# SCH_Aether_Zero_R0_5.net
KiCad netlist of a schematic drawn in EasyEDA
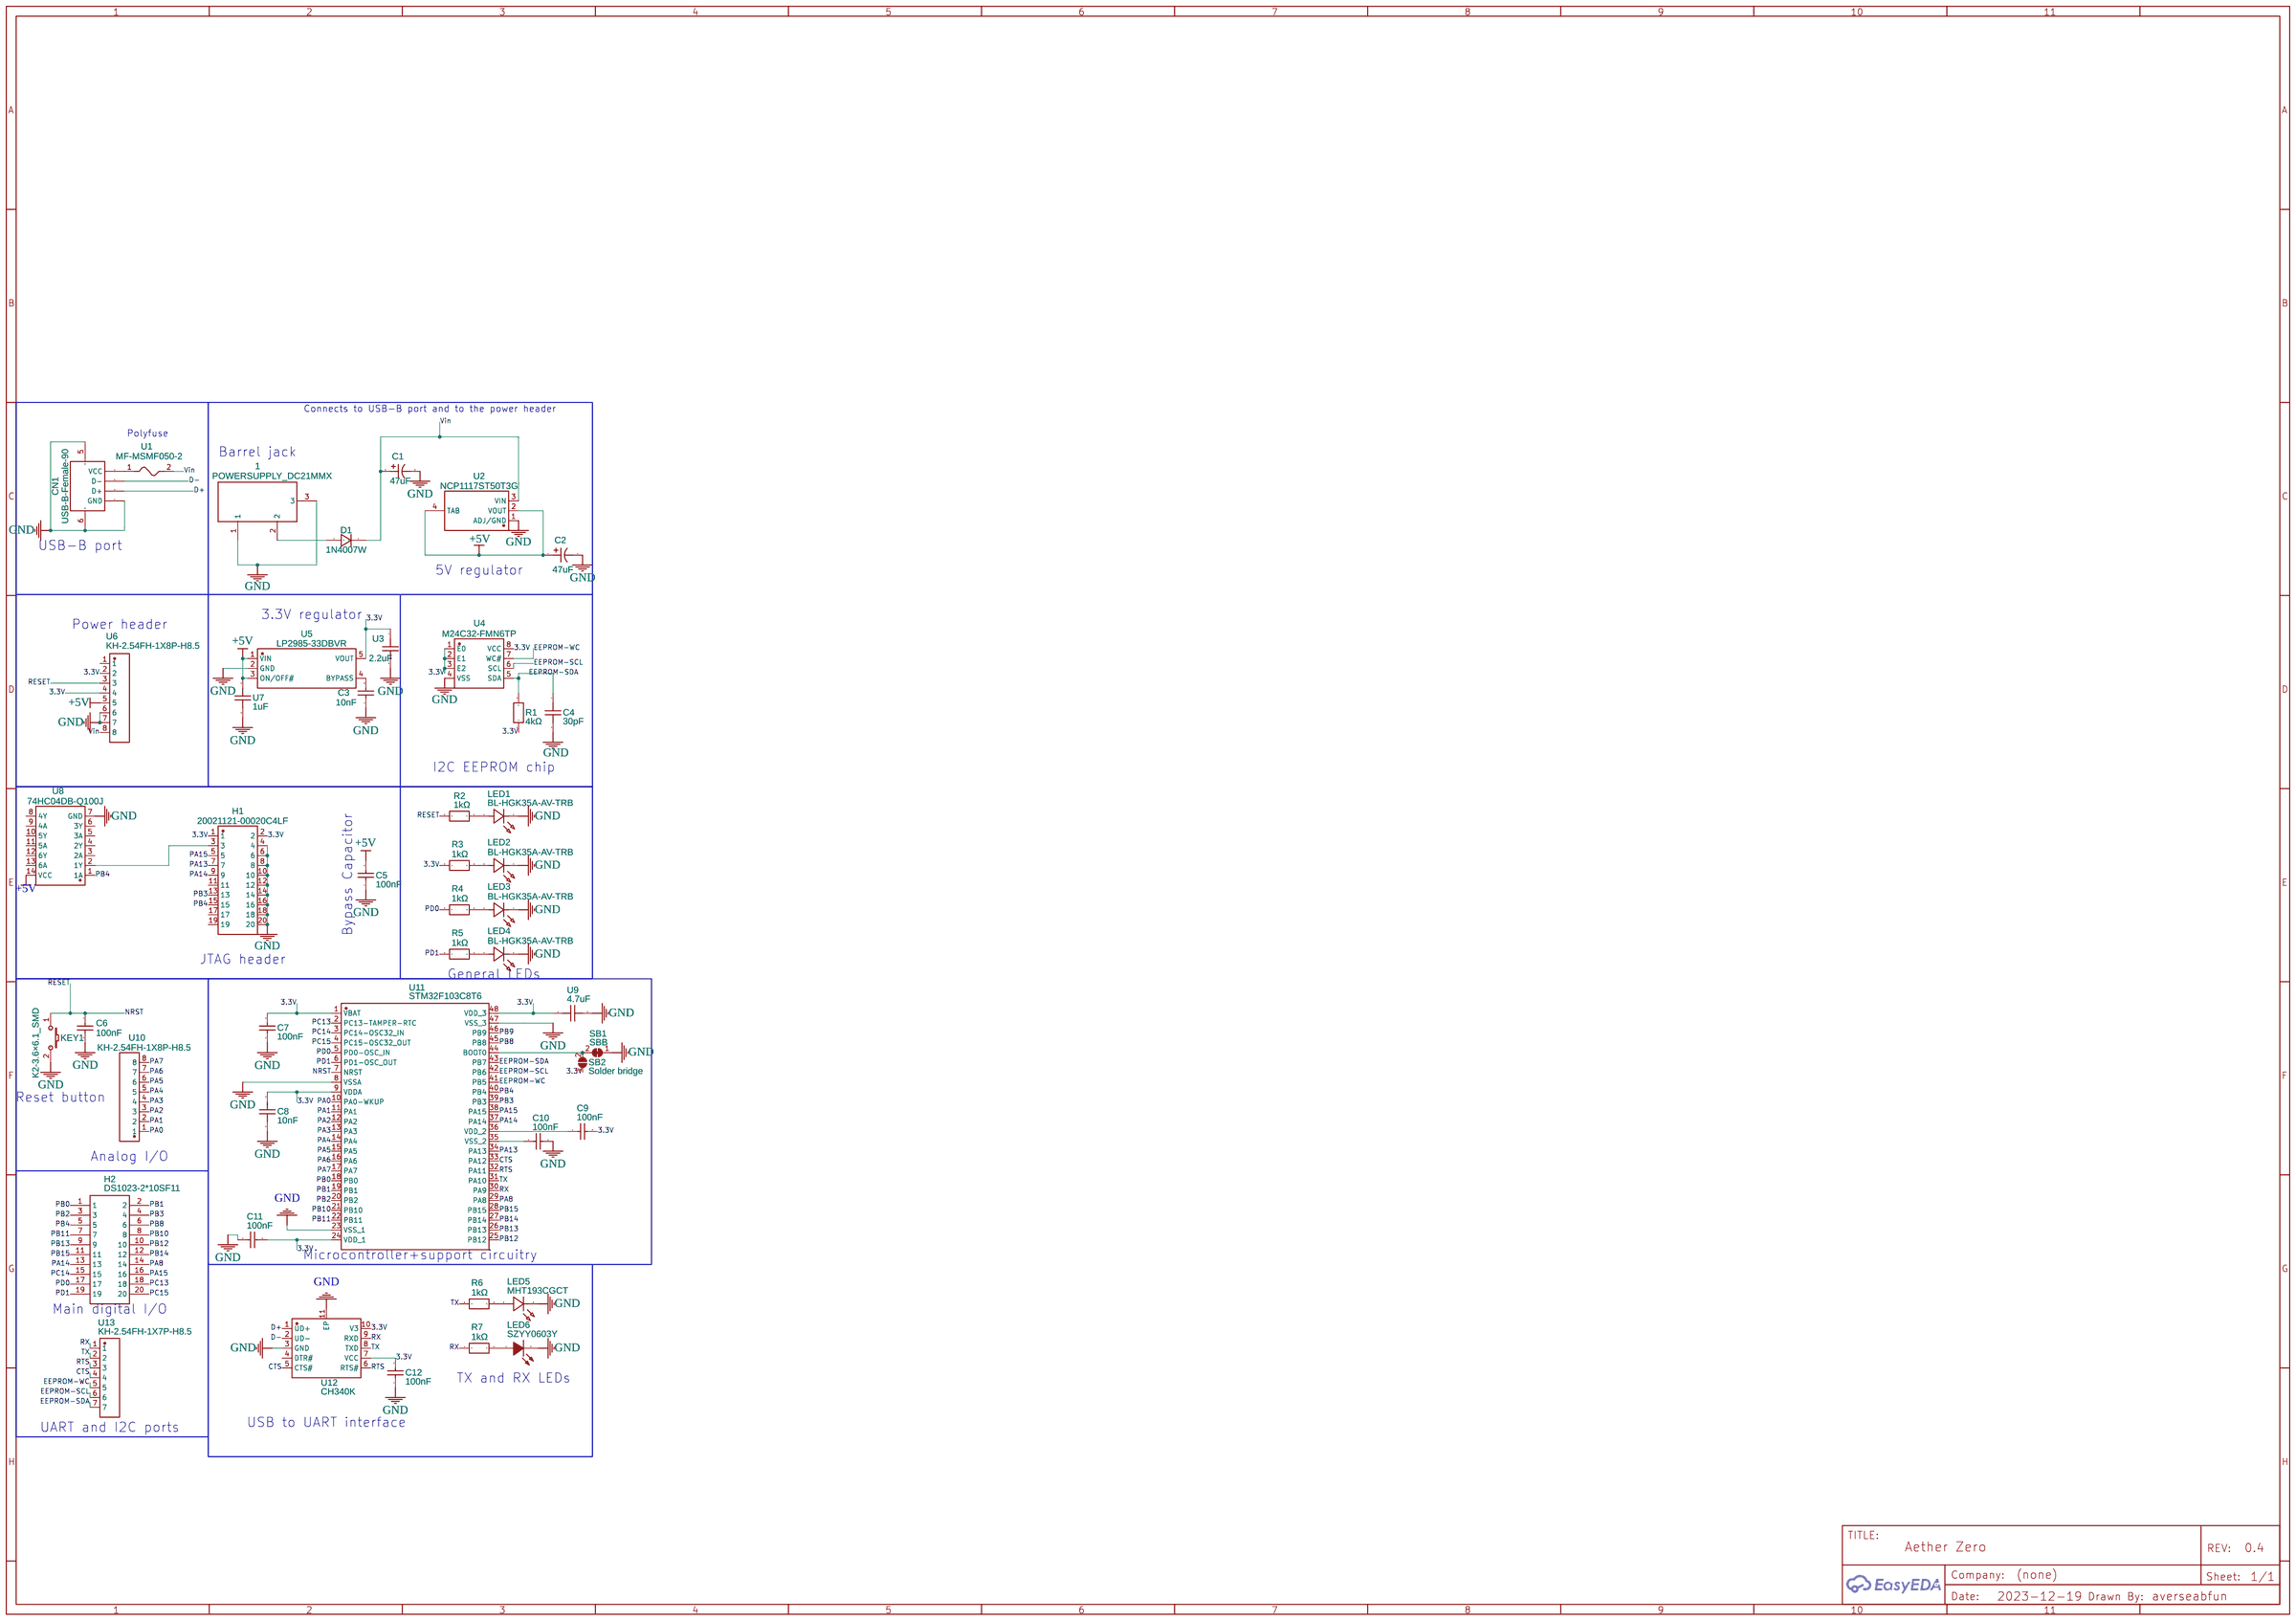
[diagram p0: schematic sheet]

(export (version "E")
  (design (tool "Eeschema 10.0.6"))
  (components
    (comp (ref "1") (value "POWERSUPPLY_DC21MMX") (libsource (lib "") (part "POWERSUPPLY_DC21MMX")))
    (comp (ref "C1")
      (value "47uF")
      (fields
        (field (name "Manufacturer Part") "RVT47UF35V67RV0039")
        (field (name "Manufacturer") "KNSCHA(科尼盛)")
      )
      (libsource (lib "") (part "RVT47UF35V67RV0039"))
    )
    (comp (ref "C2")
      (value "47uF")
      (fields
        (field (name "Manufacturer Part") "RVT47UF35V67RV0039")
        (field (name "Manufacturer") "KNSCHA(科尼盛)")
      )
      (libsource (lib "") (part "RVT47UF35V67RV0039"))
    )
    (comp (ref "C3")
      (value "10nF")
      (fields (field (name "Manufacturer Part") "0402B103K500NT") (field (name "Manufacturer") "FH(风华)"))
      (libsource (lib "") (part "0402B103K500NT"))
    )
    (comp (ref "C4")
      (value "30pF")
      (fields
        (field (name "Manufacturer Part") "AC0402JRNPO9BN300")
        (field (name "Manufacturer") "YAGEO(国巨)")
      )
      (libsource (lib "") (part "AC0402JRNPO9BN300"))
    )
    (comp (ref "C5")
      (value "100nF")
      (fields (field (name "Manufacturer Part") "0402B104K160NT") (field (name "Manufacturer") "FH(风华)"))
      (libsource (lib "") (part "0402B104K160NT_2"))
    )
    (comp (ref "C6")
      (value "100nF")
      (fields (field (name "Manufacturer Part") "0402B104K160NT") (field (name "Manufacturer") "FH(风华)"))
      (libsource (lib "") (part "0402B104K160NT"))
    )
    (comp (ref "C7")
      (value "100nF")
      (fields (field (name "Manufacturer Part") "0402B104K160NT") (field (name "Manufacturer") "FH(风华)"))
      (libsource (lib "") (part "0402B104K160NT"))
    )
    (comp (ref "C8")
      (value "10nF")
      (fields
        (field (name "Manufacturer Part") "CC0805KRX7R8BB103")
        (field (name "Manufacturer") "YAGEO(国巨)")
      )
      (libsource (lib "") (part "CC0805KRX7R8BB103"))
    )
    (comp (ref "C9")
      (value "100nF")
      (fields (field (name "Manufacturer Part") "0402B104K160NT") (field (name "Manufacturer") "FH(风华)"))
      (libsource (lib "") (part "0402B104K160NT_1"))
    )
    (comp (ref "C10")
      (value "100nF")
      (fields (field (name "Manufacturer Part") "0402B104K160NT") (field (name "Manufacturer") "FH(风华)"))
      (libsource (lib "") (part "0402B104K160NT_1"))
    )
    (comp (ref "C11")
      (value "100nF")
      (fields (field (name "Manufacturer Part") "0402B104K160NT") (field (name "Manufacturer") "FH(风华)"))
      (libsource (lib "") (part "0402B104K160NT_1"))
    )
    (comp (ref "C12")
      (value "100nF")
      (fields (field (name "Manufacturer Part") "0402B104K160NT") (field (name "Manufacturer") "FH(风华)"))
      (libsource (lib "") (part "0402B104K160NT_2"))
    )
    (comp (ref "CN1")
      (value "USB-B-Female-90")
      (fields (field (name "Manufacturer Part") "921-111A1010D10200") (field (name "Manufacturer") "精拓金"))
      (libsource (lib "") (part "USB-B-Female-90"))
    )
    (comp (ref "D1")
      (value "1N4007W")
      (fields (field (name "Manufacturer") "BLUE ROCKET"))
      (libsource (lib "") (part "1N4007W"))
    )
    (comp (ref "H1")
      (value "20021121-00020C4LF")
      (fields (field (name "Manufacturer") "Amphenol"))
      (libsource (lib "") (part "20021121-00020C4LF"))
    )
    (comp (ref "H2")
      (value "DS1023-2*10SF11")
      (fields (field (name "Manufacturer") "CONNFLY"))
      (libsource (lib "") (part "DS1023-2*10SF11"))
    )
    (comp (ref "KEY1")
      (value "K2-3.6×6.1_SMD")
      (fields (field (name "Manufacturer Part") "K2-1107ST-A4SW-06"))
      (libsource (lib "") (part "K2-3.6×6.1_SMD"))
    )
    (comp (ref "LED1")
      (value "BL-HGK35A-AV-TRB")
      (fields (field (name "Manufacturer") "BrtLed(佰鸿)"))
      (libsource (lib "") (part "BL-HGK35A-AV-TRB"))
    )
    (comp (ref "LED2")
      (value "BL-HGK35A-AV-TRB")
      (fields (field (name "Manufacturer") "BrtLed(佰鸿)"))
      (libsource (lib "") (part "BL-HGK35A-AV-TRB"))
    )
    (comp (ref "LED3")
      (value "BL-HGK35A-AV-TRB")
      (fields (field (name "Manufacturer") "BrtLed(佰鸿)"))
      (libsource (lib "") (part "BL-HGK35A-AV-TRB"))
    )
    (comp (ref "LED4")
      (value "BL-HGK35A-AV-TRB")
      (fields (field (name "Manufacturer") "BrtLed(佰鸿)"))
      (libsource (lib "") (part "BL-HGK35A-AV-TRB"))
    )
    (comp (ref "LED5")
      (value "MHT193CGCT")
      (fields (field (name "Manufacturer") "MEIHUA(美华)"))
      (libsource (lib "") (part "MHT193CGCT"))
    )
    (comp (ref "LED6")
      (value "SZYY0603Y")
      (fields (field (name "Manufacturer") "yongyu(永裕光电)"))
      (libsource (lib "") (part "SZYY0603Y"))
    )
    (comp (ref "R1")
      (value "4kΩ")
      (fields (field (name "Manufacturer Part") "RN732BTTD4001B25") (field (name "Manufacturer") "KOA"))
      (libsource (lib "") (part "RN732BTTD4001B25"))
    )
    (comp (ref "R2")
      (value "1kΩ")
      (fields (field (name "Manufacturer Part") "CR-03JA7----1K") (field (name "Manufacturer") "Viking Tech"))
      (libsource (lib "") (part "CR-03JA7----1K_1"))
    )
    (comp (ref "R3")
      (value "1kΩ")
      (fields (field (name "Manufacturer Part") "CR-03JA7----1K") (field (name "Manufacturer") "Viking Tech"))
      (libsource (lib "") (part "CR-03JA7----1K"))
    )
    (comp (ref "R4")
      (value "1kΩ")
      (fields (field (name "Manufacturer Part") "CR-03JA7----1K") (field (name "Manufacturer") "Viking Tech"))
      (libsource (lib "") (part "CR-03JA7----1K"))
    )
    (comp (ref "R5")
      (value "1kΩ")
      (fields (field (name "Manufacturer Part") "CR-03JA7----1K") (field (name "Manufacturer") "Viking Tech"))
      (libsource (lib "") (part "CR-03JA7----1K"))
    )
    (comp (ref "R6")
      (value "1kΩ")
      (fields (field (name "Manufacturer Part") "CR-03JA7----1K") (field (name "Manufacturer") "Viking Tech"))
      (libsource (lib "") (part "CR-03JA7----1K"))
    )
    (comp (ref "R7")
      (value "1kΩ")
      (fields (field (name "Manufacturer Part") "CR-03JA7----1K") (field (name "Manufacturer") "Viking Tech"))
      (libsource (lib "") (part "CR-03JA7----1K"))
    )
    (comp (ref "SB1") (value "SBB") (libsource (lib "") (part "SBB")))
    (comp (ref "SB2")
      (value "Solder bridge")
      (fields (field (name "Manufacturer Part") "DNP"))
      (libsource (lib "") (part "Solder bridge"))
    )
    (comp (ref "U1")
      (value "MF-MSMF050-2")
      (fields (field (name "Manufacturer") "BOURNS"))
      (libsource (lib "") (part "MF-MSMF050-2"))
    )
    (comp (ref "U2")
      (value "NCP1117ST50T3G")
      (fields (field (name "Manufacturer") "onsemi(安森美)"))
      (libsource (lib "") (part "NCP1117ST50T3G"))
    )
    (comp (ref "U3")
      (value "2.2uF")
      (fields (field (name "Manufacturer Part") "0805X225K250CT") (field (name "Manufacturer") "Walsin(华新科)"))
      (libsource (lib "") (part "0805X225K250CT_C5122273"))
    )
    (comp (ref "U4")
      (value "M24C32-FMN6TP")
      (fields (field (name "Manufacturer") "ST(意法半导体)"))
      (libsource (lib "") (part "M24C32-FMN6TP"))
    )
    (comp (ref "U5")
      (value "LP2985-33DBVR")
      (fields (field (name "Manufacturer") "TI(德州仪器)"))
      (libsource (lib "") (part "LP2985-33DBVR"))
    )
    (comp (ref "U6")
      (value "KH-2.54FH-1X8P-H8.5")
      (fields (field (name "Manufacturer") "kinghelm(金航标)"))
      (libsource (lib "") (part "KH-2.54FH-1X8P-H8.5"))
    )
    (comp (ref "U7")
      (value "1uF")
      (fields (field (name "Manufacturer Part") "CGA5L3X8R1H105KT0Y0N") (field (name "Manufacturer") "TDK"))
      (libsource (lib "") (part "CGA5L3X8R1H105KT0Y0N"))
    )
    (comp (ref "U8")
      (value "74HC04DB-Q100J")
      (fields (field (name "Manufacturer") "Nexperia(安世)"))
      (libsource (lib "") (part "74HC04DB-Q100J"))
    )
    (comp (ref "U9")
      (value "4.7uF")
      (fields
        (field (name "Manufacturer Part") "CSA0603X5R475K6R3JT")
        (field (name "Manufacturer") "HRE(芯声)")
      )
      (libsource (lib "") (part "CSA0603X5R475K6R3JT"))
    )
    (comp (ref "U10")
      (value "KH-2.54FH-1X8P-H8.5")
      (fields (field (name "Manufacturer") "kinghelm(金航标)"))
      (libsource (lib "") (part "KH-2.54FH-1X8P-H8.5_1"))
    )
    (comp (ref "U11")
      (value "STM32F103C8T6")
      (fields (field (name "Manufacturer") "ST(意法半导体)"))
      (libsource (lib "") (part "STM32F103C8T6"))
    )
    (comp (ref "U12")
      (value "CH340K")
      (fields (field (name "Manufacturer") "WCH(南京沁恒)"))
      (libsource (lib "") (part "CH340K"))
    )
    (comp (ref "U13")
      (value "KH-2.54FH-1X7P-H8.5")
      (fields (field (name "Manufacturer") "kinghelm(金航标)"))
      (libsource (lib "") (part "KH-2.54FH-1X7P-H8.5"))
    )
  )
  (nets
    (net (code "1") (name "+5V") (class "Default")
      (node (ref "C2") (pin "1") (pinfunction "1_1") (pintype "input"))
      (node (ref "C5") (pin "2") (pinfunction "2_2") (pintype "input"))
      (node (ref "U2") (pin "2") (pinfunction "VOUT_2") (pintype "unspecified"))
      (node (ref "U2") (pin "4") (pinfunction "TAB_4") (pintype "unspecified"))
      (node (ref "U5") (pin "1") (pinfunction "VIN_1") (pintype "unspecified"))
      (node (ref "U5") (pin "3") (pinfunction "ON/OFF#_3") (pintype "unspecified"))
      (node (ref "U6") (pin "5") (pinfunction "5_5") (pintype "unspecified"))
      (node (ref "U7") (pin "2") (pinfunction "2_2") (pintype "unspecified"))
      (node (ref "U8") (pin "14") (pinfunction "VCC_14") (pintype "unspecified"))
    )
    (net (code "2") (name "/3.3V") (class "Default")
      (node (ref "C11") (pin "2") (pinfunction "2_2") (pintype "input"))
      (node (ref "C12") (pin "2") (pinfunction "2_2") (pintype "input"))
      (node (ref "C7") (pin "1") (pinfunction "1_1") (pintype "input"))
      (node (ref "C8") (pin "2") (pinfunction "2_2") (pintype "unspecified"))
      (node (ref "C9") (pin "2") (pinfunction "2_2") (pintype "input"))
      (node (ref "H1") (pin "1") (pinfunction "1_1") (pintype "unspecified"))
      (node (ref "H1") (pin "2") (pinfunction "2_2") (pintype "unspecified"))
      (node (ref "R1") (pin "1") (pinfunction "1_1") (pintype "unspecified"))
      (node (ref "R3") (pin "1") (pinfunction "1_1") (pintype "unspecified"))
      (node (ref "SB2") (pin "1") (pinfunction "A_1") (pintype "unspecified"))
      (node (ref "U11") (pin "1") (pinfunction "VBAT_1") (pintype "unspecified"))
      (node (ref "U11") (pin "24") (pinfunction "VDD_1_24") (pintype "unspecified"))
      (node (ref "U11") (pin "48") (pinfunction "VDD_3_48") (pintype "unspecified"))
      (node (ref "U11") (pin "9") (pinfunction "VDDA_9") (pintype "unspecified"))
      (node (ref "U12") (pin "10") (pinfunction "V3_10") (pintype "unspecified"))
      (node (ref "U12") (pin "7") (pinfunction "VCC_7") (pintype "unspecified"))
      (node (ref "U3") (pin "1") (pinfunction "1_1") (pintype "unspecified"))
      (node (ref "U4") (pin "1") (pinfunction "E0_1") (pintype "unspecified"))
      (node (ref "U4") (pin "2") (pinfunction "E1_2") (pintype "unspecified"))
      (node (ref "U4") (pin "3") (pinfunction "E2_3") (pintype "unspecified"))
      (node (ref "U4") (pin "8") (pinfunction "VCC_8") (pintype "unspecified"))
      (node (ref "U5") (pin "5") (pinfunction "VOUT_5") (pintype "unspecified"))
      (node (ref "U6") (pin "2") (pinfunction "2_2") (pintype "unspecified"))
      (node (ref "U6") (pin "4") (pinfunction "4_4") (pintype "unspecified"))
      (node (ref "U9") (pin "1") (pinfunction "1_1") (pintype "unspecified"))
    )
    (net (code "3") (name "/CTS") (class "Default")
      (node (ref "U11") (pin "33") (pinfunction "PA12_33") (pintype "unspecified"))
      (node (ref "U12") (pin "5") (pinfunction "CTS#_5") (pintype "unspecified"))
      (node (ref "U13") (pin "4") (pinfunction "4_4") (pintype "unspecified"))
    )
    (net (code "4") (name "/D+") (class "Default")
      (node (ref "CN1") (pin "3") (pinfunction "D+_3") (pintype "input"))
      (node (ref "U12") (pin "1") (pinfunction "UD+_1") (pintype "unspecified"))
    )
    (net (code "5") (name "/D-") (class "Default")
      (node (ref "CN1") (pin "2") (pinfunction "D-_2") (pintype "input"))
      (node (ref "U12") (pin "2") (pinfunction "UD-_2") (pintype "unspecified"))
    )
    (net (code "6") (name "/EEPROM-SCL") (class "Default")
      (node (ref "U11") (pin "42") (pinfunction "PB6_42") (pintype "unspecified"))
      (node (ref "U13") (pin "6") (pinfunction "6_6") (pintype "unspecified"))
      (node (ref "U4") (pin "6") (pinfunction "SCL_6") (pintype "unspecified"))
    )
    (net (code "7") (name "/EEPROM-SDA") (class "Default")
      (node (ref "C4") (pin "1") (pinfunction "1_1") (pintype "unspecified"))
      (node (ref "R1") (pin "2") (pinfunction "2_2") (pintype "unspecified"))
      (node (ref "U11") (pin "43") (pinfunction "PB7_43") (pintype "unspecified"))
      (node (ref "U13") (pin "7") (pinfunction "7_7") (pintype "unspecified"))
      (node (ref "U4") (pin "5") (pinfunction "SDA_5") (pintype "unspecified"))
    )
    (net (code "8") (name "/EEPROM-WC") (class "Default")
      (node (ref "U11") (pin "41") (pinfunction "PB5_41") (pintype "unspecified"))
      (node (ref "U13") (pin "5") (pinfunction "5_5") (pintype "unspecified"))
      (node (ref "U4") (pin "7") (pinfunction "WC#_7") (pintype "unspecified"))
    )
    (net (code "9") (name "/NRST") (class "Default")
      (node (ref "C6") (pin "1") (pinfunction "1_1") (pintype "input"))
      (node (ref "KEY1") (pin "1") (pinfunction "1_1") (pintype "unspecified"))
      (node (ref "R2") (pin "2") (pinfunction "2_2") (pintype "unspecified"))
      (node (ref "U11") (pin "7") (pinfunction "NRST_7") (pintype "unspecified"))
      (node (ref "U6") (pin "3") (pinfunction "3_3") (pintype "unspecified"))
    )
    (net (code "10") (name "/PA0") (class "Default")
      (node (ref "U10") (pin "1") (pinfunction "1_1") (pintype "unspecified"))
      (node (ref "U11") (pin "10") (pinfunction "PA0-WKUP_10") (pintype "unspecified"))
    )
    (net (code "11") (name "/PA1") (class "Default")
      (node (ref "U10") (pin "2") (pinfunction "2_2") (pintype "unspecified"))
      (node (ref "U11") (pin "11") (pinfunction "PA1_11") (pintype "unspecified"))
    )
    (net (code "12") (name "/PA2") (class "Default")
      (node (ref "U10") (pin "3") (pinfunction "3_3") (pintype "unspecified"))
      (node (ref "U11") (pin "12") (pinfunction "PA2_12") (pintype "unspecified"))
    )
    (net (code "13") (name "/PA3") (class "Default")
      (node (ref "U10") (pin "4") (pinfunction "4_4") (pintype "unspecified"))
      (node (ref "U11") (pin "13") (pinfunction "PA3_13") (pintype "unspecified"))
    )
    (net (code "14") (name "/PA4") (class "Default")
      (node (ref "U10") (pin "5") (pinfunction "5_5") (pintype "unspecified"))
      (node (ref "U11") (pin "14") (pinfunction "PA4_14") (pintype "unspecified"))
    )
    (net (code "15") (name "/PA5") (class "Default")
      (node (ref "U10") (pin "6") (pinfunction "6_6") (pintype "unspecified"))
      (node (ref "U11") (pin "15") (pinfunction "PA5_15") (pintype "unspecified"))
    )
    (net (code "16") (name "/PA6") (class "Default")
      (node (ref "U10") (pin "7") (pinfunction "7_7") (pintype "unspecified"))
      (node (ref "U11") (pin "16") (pinfunction "PA6_16") (pintype "unspecified"))
    )
    (net (code "17") (name "/PA7") (class "Default")
      (node (ref "U10") (pin "8") (pinfunction "8_8") (pintype "unspecified"))
      (node (ref "U11") (pin "17") (pinfunction "PA7_17") (pintype "unspecified"))
    )
    (net (code "18") (name "/PA8") (class "Default")
      (node (ref "H2") (pin "14") (pinfunction "14_14") (pintype "unspecified"))
      (node (ref "U11") (pin "29") (pinfunction "PA8_29") (pintype "unspecified"))
    )
    (net (code "19") (name "/PA13") (class "Default")
      (node (ref "H1") (pin "7") (pinfunction "7_7") (pintype "unspecified"))
      (node (ref "U11") (pin "34") (pinfunction "PA13_34") (pintype "unspecified"))
    )
    (net (code "20") (name "/PA14") (class "Default")
      (node (ref "H1") (pin "9") (pinfunction "9_9") (pintype "unspecified"))
      (node (ref "H2") (pin "13") (pinfunction "13_13") (pintype "unspecified"))
      (node (ref "U11") (pin "37") (pinfunction "PA14_37") (pintype "unspecified"))
    )
    (net (code "21") (name "/PA15") (class "Default")
      (node (ref "H1") (pin "5") (pinfunction "5_5") (pintype "unspecified"))
      (node (ref "H2") (pin "16") (pinfunction "16_16") (pintype "unspecified"))
      (node (ref "U11") (pin "38") (pinfunction "PA15_38") (pintype "unspecified"))
    )
    (net (code "22") (name "/PB0") (class "Default")
      (node (ref "H2") (pin "1") (pinfunction "1_1") (pintype "unspecified"))
      (node (ref "U11") (pin "18") (pinfunction "PB0_18") (pintype "unspecified"))
    )
    (net (code "23") (name "/PB1") (class "Default")
      (node (ref "H2") (pin "2") (pinfunction "2_2") (pintype "unspecified"))
      (node (ref "U11") (pin "19") (pinfunction "PB1_19") (pintype "unspecified"))
    )
    (net (code "24") (name "/PB2") (class "Default")
      (node (ref "H2") (pin "3") (pinfunction "3_3") (pintype "unspecified"))
      (node (ref "U11") (pin "20") (pinfunction "PB2_20") (pintype "unspecified"))
    )
    (net (code "25") (name "/PB3") (class "Default")
      (node (ref "H1") (pin "13") (pinfunction "13_13") (pintype "unspecified"))
      (node (ref "H2") (pin "4") (pinfunction "4_4") (pintype "unspecified"))
      (node (ref "U11") (pin "39") (pinfunction "PB3_39") (pintype "unspecified"))
    )
    (net (code "26") (name "/PB4") (class "Default")
      (node (ref "H1") (pin "15") (pinfunction "15_15") (pintype "unspecified"))
      (node (ref "H2") (pin "5") (pinfunction "5_5") (pintype "unspecified"))
      (node (ref "U11") (pin "40") (pinfunction "PB4_40") (pintype "unspecified"))
      (node (ref "U8") (pin "1") (pinfunction "1A_1") (pintype "unspecified"))
    )
    (net (code "27") (name "/PB8") (class "Default")
      (node (ref "H2") (pin "6") (pinfunction "6_6") (pintype "unspecified"))
      (node (ref "U11") (pin "45") (pinfunction "PB8_45") (pintype "unspecified"))
    )
    (net (code "28") (name "/PB9") (class "Default")
      (node (ref "U11") (pin "46") (pinfunction "PB9_46") (pintype "unspecified"))
    )
    (net (code "29") (name "/PB10") (class "Default")
      (node (ref "H2") (pin "8") (pinfunction "8_8") (pintype "unspecified"))
      (node (ref "U11") (pin "21") (pinfunction "PB10_21") (pintype "unspecified"))
    )
    (net (code "30") (name "/PB11") (class "Default")
      (node (ref "H2") (pin "7") (pinfunction "7_7") (pintype "unspecified"))
      (node (ref "U11") (pin "22") (pinfunction "PB11_22") (pintype "unspecified"))
    )
    (net (code "31") (name "/PB12") (class "Default")
      (node (ref "H2") (pin "10") (pinfunction "10_10") (pintype "unspecified"))
      (node (ref "U11") (pin "25") (pinfunction "PB12_25") (pintype "unspecified"))
    )
    (net (code "32") (name "/PB13") (class "Default")
      (node (ref "H2") (pin "9") (pinfunction "9_9") (pintype "unspecified"))
      (node (ref "U11") (pin "26") (pinfunction "PB13_26") (pintype "unspecified"))
    )
    (net (code "33") (name "/PB14") (class "Default")
      (node (ref "H2") (pin "12") (pinfunction "12_12") (pintype "unspecified"))
      (node (ref "U11") (pin "27") (pinfunction "PB14_27") (pintype "unspecified"))
    )
    (net (code "34") (name "/PB15") (class "Default")
      (node (ref "H2") (pin "11") (pinfunction "11_11") (pintype "unspecified"))
      (node (ref "U11") (pin "28") (pinfunction "PB15_28") (pintype "unspecified"))
    )
    (net (code "35") (name "/PC13") (class "Default")
      (node (ref "H2") (pin "18") (pinfunction "18_18") (pintype "unspecified"))
      (node (ref "U11") (pin "2") (pinfunction "PC13-TAMPER-RTC_2") (pintype "unspecified"))
    )
    (net (code "36") (name "/PC14") (class "Default")
      (node (ref "H2") (pin "15") (pinfunction "15_15") (pintype "unspecified"))
      (node (ref "U11") (pin "3") (pinfunction "PC14-OSC32_IN_3") (pintype "unspecified"))
    )
    (net (code "37") (name "/PC15") (class "Default")
      (node (ref "H2") (pin "20") (pinfunction "20_20") (pintype "unspecified"))
      (node (ref "U11") (pin "4") (pinfunction "PC15-OSC32_OUT_4") (pintype "unspecified"))
    )
    (net (code "38") (name "/PD0") (class "Default")
      (node (ref "H2") (pin "17") (pinfunction "17_17") (pintype "unspecified"))
      (node (ref "R4") (pin "1") (pinfunction "1_1") (pintype "unspecified"))
      (node (ref "U11") (pin "5") (pinfunction "PD0-OSC_IN_5") (pintype "unspecified"))
    )
    (net (code "39") (name "/PD1") (class "Default")
      (node (ref "H2") (pin "19") (pinfunction "19_19") (pintype "unspecified"))
      (node (ref "R5") (pin "1") (pinfunction "1_1") (pintype "unspecified"))
      (node (ref "U11") (pin "6") (pinfunction "PD1-OSC_OUT_6") (pintype "unspecified"))
    )
    (net (code "40") (name "/RTS") (class "Default")
      (node (ref "U11") (pin "32") (pinfunction "PA11_32") (pintype "unspecified"))
      (node (ref "U12") (pin "6") (pinfunction "RTS#_6") (pintype "unspecified"))
      (node (ref "U13") (pin "3") (pinfunction "3_3") (pintype "unspecified"))
    )
    (net (code "41") (name "/RX") (class "Default")
      (node (ref "R7") (pin "1") (pinfunction "1_1") (pintype "unspecified"))
      (node (ref "U11") (pin "30") (pinfunction "PA9_30") (pintype "unspecified"))
      (node (ref "U12") (pin "9") (pinfunction "RXD_9") (pintype "unspecified"))
      (node (ref "U13") (pin "1") (pinfunction "1_1") (pintype "unspecified"))
    )
    (net (code "42") (name "/TX") (class "Default")
      (node (ref "R6") (pin "1") (pinfunction "1_1") (pintype "unspecified"))
      (node (ref "U11") (pin "31") (pinfunction "PA10_31") (pintype "unspecified"))
      (node (ref "U12") (pin "8") (pinfunction "TXD_8") (pintype "unspecified"))
      (node (ref "U13") (pin "2") (pinfunction "2_2") (pintype "unspecified"))
    )
    (net (code "43") (name "/Vin") (class "Default")
      (node (ref "C1") (pin "1") (pinfunction "1_1") (pintype "input"))
      (node (ref "D1") (pin "1") (pinfunction "1_1") (pintype "unspecified"))
      (node (ref "U1") (pin "2") (pinfunction "2_2") (pintype "unspecified"))
      (node (ref "U2") (pin "3") (pinfunction "VIN_3") (pintype "unspecified"))
      (node (ref "U6") (pin "8") (pinfunction "8_8") (pintype "unspecified"))
    )
    (net (code "44") (name "GND") (class "Default")
      (node (ref "1") (pin "1") (pinfunction "1_1") (pintype "bidirectional"))
      (node (ref "1") (pin "3") (pinfunction "3_3") (pintype "bidirectional"))
      (node (ref "C1") (pin "2") (pinfunction "2_2") (pintype "input"))
      (node (ref "C10") (pin "2") (pinfunction "2_2") (pintype "input"))
      (node (ref "C11") (pin "1") (pinfunction "1_1") (pintype "input"))
      (node (ref "C12") (pin "1") (pinfunction "1_1") (pintype "input"))
      (node (ref "C2") (pin "2") (pinfunction "2_2") (pintype "input"))
      (node (ref "C3") (pin "1") (pinfunction "1_1") (pintype "input"))
      (node (ref "C4") (pin "2") (pinfunction "2_2") (pintype "unspecified"))
      (node (ref "C5") (pin "1") (pinfunction "1_1") (pintype "input"))
      (node (ref "C6") (pin "2") (pinfunction "2_2") (pintype "input"))
      (node (ref "C7") (pin "2") (pinfunction "2_2") (pintype "input"))
      (node (ref "C8") (pin "1") (pinfunction "1_1") (pintype "unspecified"))
      (node (ref "CN1") (pin "4") (pinfunction "GND_4") (pintype "input"))
      (node (ref "CN1") (pin "5") (pinfunction "SH1_5") (pintype "unspecified"))
      (node (ref "CN1") (pin "6") (pinfunction "SH2_6") (pintype "unspecified"))
      (node (ref "H1") (pin "10") (pinfunction "10_10") (pintype "unspecified"))
      (node (ref "H1") (pin "12") (pinfunction "12_12") (pintype "unspecified"))
      (node (ref "H1") (pin "14") (pinfunction "14_14") (pintype "unspecified"))
      (node (ref "H1") (pin "16") (pinfunction "16_16") (pintype "unspecified"))
      (node (ref "H1") (pin "18") (pinfunction "18_18") (pintype "unspecified"))
      (node (ref "H1") (pin "20") (pinfunction "20_20") (pintype "unspecified"))
      (node (ref "H1") (pin "4") (pinfunction "4_4") (pintype "unspecified"))
      (node (ref "H1") (pin "6") (pinfunction "6_6") (pintype "unspecified"))
      (node (ref "H1") (pin "8") (pinfunction "8_8") (pintype "unspecified"))
      (node (ref "KEY1") (pin "2") (pinfunction "2_2") (pintype "unspecified"))
      (node (ref "LED1") (pin "1") (pinfunction "K_1") (pintype "unspecified"))
      (node (ref "LED2") (pin "1") (pinfunction "K_1") (pintype "unspecified"))
      (node (ref "LED3") (pin "1") (pinfunction "K_1") (pintype "unspecified"))
      (node (ref "LED4") (pin "1") (pinfunction "K_1") (pintype "unspecified"))
      (node (ref "LED5") (pin "1") (pinfunction "K_1") (pintype "unspecified"))
      (node (ref "LED6") (pin "2") (pinfunction "-_2") (pintype "unspecified"))
      (node (ref "SB1") (pin "1") (pinfunction "A_1") (pintype "unspecified"))
      (node (ref "U11") (pin "23") (pinfunction "VSS_1_23") (pintype "unspecified"))
      (node (ref "U11") (pin "47") (pinfunction "VSS_3_47") (pintype "unspecified"))
      (node (ref "U11") (pin "8") (pinfunction "VSSA_8") (pintype "unspecified"))
      (node (ref "U12") (pin "11") (pinfunction "EP_11") (pintype "unspecified"))
      (node (ref "U12") (pin "3") (pinfunction "GND_3") (pintype "unspecified"))
      (node (ref "U2") (pin "1") (pinfunction "ADJ/GND_1") (pintype "unspecified"))
      (node (ref "U3") (pin "2") (pinfunction "2_2") (pintype "unspecified"))
      (node (ref "U4") (pin "4") (pinfunction "VSS_4") (pintype "unspecified"))
      (node (ref "U5") (pin "2") (pinfunction "GND_2") (pintype "unspecified"))
      (node (ref "U6") (pin "6") (pinfunction "6_6") (pintype "unspecified"))
      (node (ref "U6") (pin "7") (pinfunction "7_7") (pintype "unspecified"))
      (node (ref "U7") (pin "1") (pinfunction "1_1") (pintype "unspecified"))
      (node (ref "U8") (pin "7") (pinfunction "GND_7") (pintype "unspecified"))
      (node (ref "U9") (pin "2") (pinfunction "2_2") (pintype "unspecified"))
    )
    (net (code "45") (name "Net-(1-Pad2)") (class "Default")
      (node (ref "1") (pin "2") (pinfunction "2_2") (pintype "bidirectional"))
      (node (ref "D1") (pin "2") (pinfunction "2_2") (pintype "unspecified"))
    )
    (net (code "46") (name "Net-(CN1-VCC)") (class "Default")
      (node (ref "CN1") (pin "1") (pinfunction "VCC_1") (pintype "input"))
      (node (ref "U1") (pin "1") (pinfunction "1_1") (pintype "unspecified"))
    )
    (net (code "47") (name "Net-(LED1-A)") (class "Default")
      (node (ref "LED1") (pin "2") (pinfunction "A_2") (pintype "unspecified"))
      (node (ref "R2") (pin "1") (pinfunction "1_1") (pintype "unspecified"))
    )
    (net (code "48") (name "Net-(LED2-A)") (class "Default")
      (node (ref "LED2") (pin "2") (pinfunction "A_2") (pintype "unspecified"))
      (node (ref "R3") (pin "2") (pinfunction "2_2") (pintype "unspecified"))
    )
    (net (code "49") (name "Net-(LED3-A)") (class "Default")
      (node (ref "LED3") (pin "2") (pinfunction "A_2") (pintype "unspecified"))
      (node (ref "R4") (pin "2") (pinfunction "2_2") (pintype "unspecified"))
    )
    (net (code "50") (name "Net-(LED4-A)") (class "Default")
      (node (ref "LED4") (pin "2") (pinfunction "A_2") (pintype "unspecified"))
      (node (ref "R5") (pin "2") (pinfunction "2_2") (pintype "unspecified"))
    )
    (net (code "51") (name "Net-(LED5-A)") (class "Default")
      (node (ref "LED5") (pin "2") (pinfunction "A_2") (pintype "unspecified"))
      (node (ref "R6") (pin "2") (pinfunction "2_2") (pintype "unspecified"))
    )
    (net (code "52") (name "Net-(LED6-+)") (class "Default")
      (node (ref "LED6") (pin "1") (pinfunction "+_1") (pintype "unspecified"))
      (node (ref "R7") (pin "2") (pinfunction "2_2") (pintype "unspecified"))
    )
    (net (code "53") (name "Net-(SB1-B)") (class "Default")
      (node (ref "SB1") (pin "2") (pinfunction "B_2") (pintype "unspecified"))
      (node (ref "SB2") (pin "2") (pinfunction "B_2") (pintype "unspecified"))
      (node (ref "U11") (pin "44") (pinfunction "BOOT0_44") (pintype "unspecified"))
    )
    (net (code "54") (name "Net-(U5-BYPASS)") (class "Default")
      (node (ref "C3") (pin "2") (pinfunction "2_2") (pintype "input"))
      (node (ref "U5") (pin "4") (pinfunction "BYPASS_4") (pintype "unspecified"))
    )
    (net (code "55") (name "Net-(U8-1Y)") (class "Default")
      (node (ref "H1") (pin "3") (pinfunction "3_3") (pintype "unspecified"))
      (node (ref "U8") (pin "2") (pinfunction "1Y_2") (pintype "unspecified"))
    )
    (net (code "56") (name "Net-(U11-VDD_2)") (class "Default")
      (node (ref "C9") (pin "1") (pinfunction "1_1") (pintype "input"))
      (node (ref "U11") (pin "36") (pinfunction "VDD_2_36") (pintype "unspecified"))
    )
    (net (code "57") (name "Net-(U11-VSS_2)") (class "Default")
      (node (ref "C10") (pin "1") (pinfunction "1_1") (pintype "input"))
      (node (ref "U11") (pin "35") (pinfunction "VSS_2_35") (pintype "unspecified"))
    )
    (net (code "58") (name "unconnected-(H1-Pad11)") (class "Default")
      (node (ref "H1") (pin "11") (pinfunction "11_11") (pintype "unspecified"))
    )
    (net (code "59") (name "unconnected-(H1-Pad17)") (class "Default")
      (node (ref "H1") (pin "17") (pinfunction "17_17") (pintype "unspecified"))
    )
    (net (code "60") (name "unconnected-(H1-Pad19)") (class "Default")
      (node (ref "H1") (pin "19") (pinfunction "19_19") (pintype "unspecified"))
    )
    (net (code "61") (name "unconnected-(U6-Pad1)") (class "Default")
      (node (ref "U6") (pin "1") (pinfunction "1_1") (pintype "unspecified"))
    )
    (net (code "62") (name "unconnected-(U8-2A-Pad3)") (class "Default")
      (node (ref "U8") (pin "3") (pinfunction "2A_3") (pintype "unspecified"))
    )
    (net (code "63") (name "unconnected-(U8-2Y-Pad4)") (class "Default")
      (node (ref "U8") (pin "4") (pinfunction "2Y_4") (pintype "unspecified"))
    )
    (net (code "64") (name "unconnected-(U8-3A-Pad5)") (class "Default")
      (node (ref "U8") (pin "5") (pinfunction "3A_5") (pintype "unspecified"))
    )
    (net (code "65") (name "unconnected-(U8-3Y-Pad6)") (class "Default")
      (node (ref "U8") (pin "6") (pinfunction "3Y_6") (pintype "unspecified"))
    )
    (net (code "66") (name "unconnected-(U8-4A-Pad9)") (class "Default")
      (node (ref "U8") (pin "9") (pinfunction "4A_9") (pintype "unspecified"))
    )
    (net (code "67") (name "unconnected-(U8-4Y-Pad8)") (class "Default")
      (node (ref "U8") (pin "8") (pinfunction "4Y_8") (pintype "unspecified"))
    )
    (net (code "68") (name "unconnected-(U8-5A-Pad11)") (class "Default")
      (node (ref "U8") (pin "11") (pinfunction "5A_11") (pintype "unspecified"))
    )
    (net (code "69") (name "unconnected-(U8-5Y-Pad10)") (class "Default")
      (node (ref "U8") (pin "10") (pinfunction "5Y_10") (pintype "unspecified"))
    )
    (net (code "70") (name "unconnected-(U8-6A-Pad13)") (class "Default")
      (node (ref "U8") (pin "13") (pinfunction "6A_13") (pintype "unspecified"))
    )
    (net (code "71") (name "unconnected-(U8-6Y-Pad12)") (class "Default")
      (node (ref "U8") (pin "12") (pinfunction "6Y_12") (pintype "unspecified"))
    )
    (net (code "72") (name "unconnected-(U12-DTR#-Pad4)") (class "Default")
      (node (ref "U12") (pin "4") (pinfunction "DTR#_4") (pintype "unspecified"))
    )
  )
)
